# SenseBox-MCU-2-0.net
KiCad netlist of a schematic drawn in EAGLE
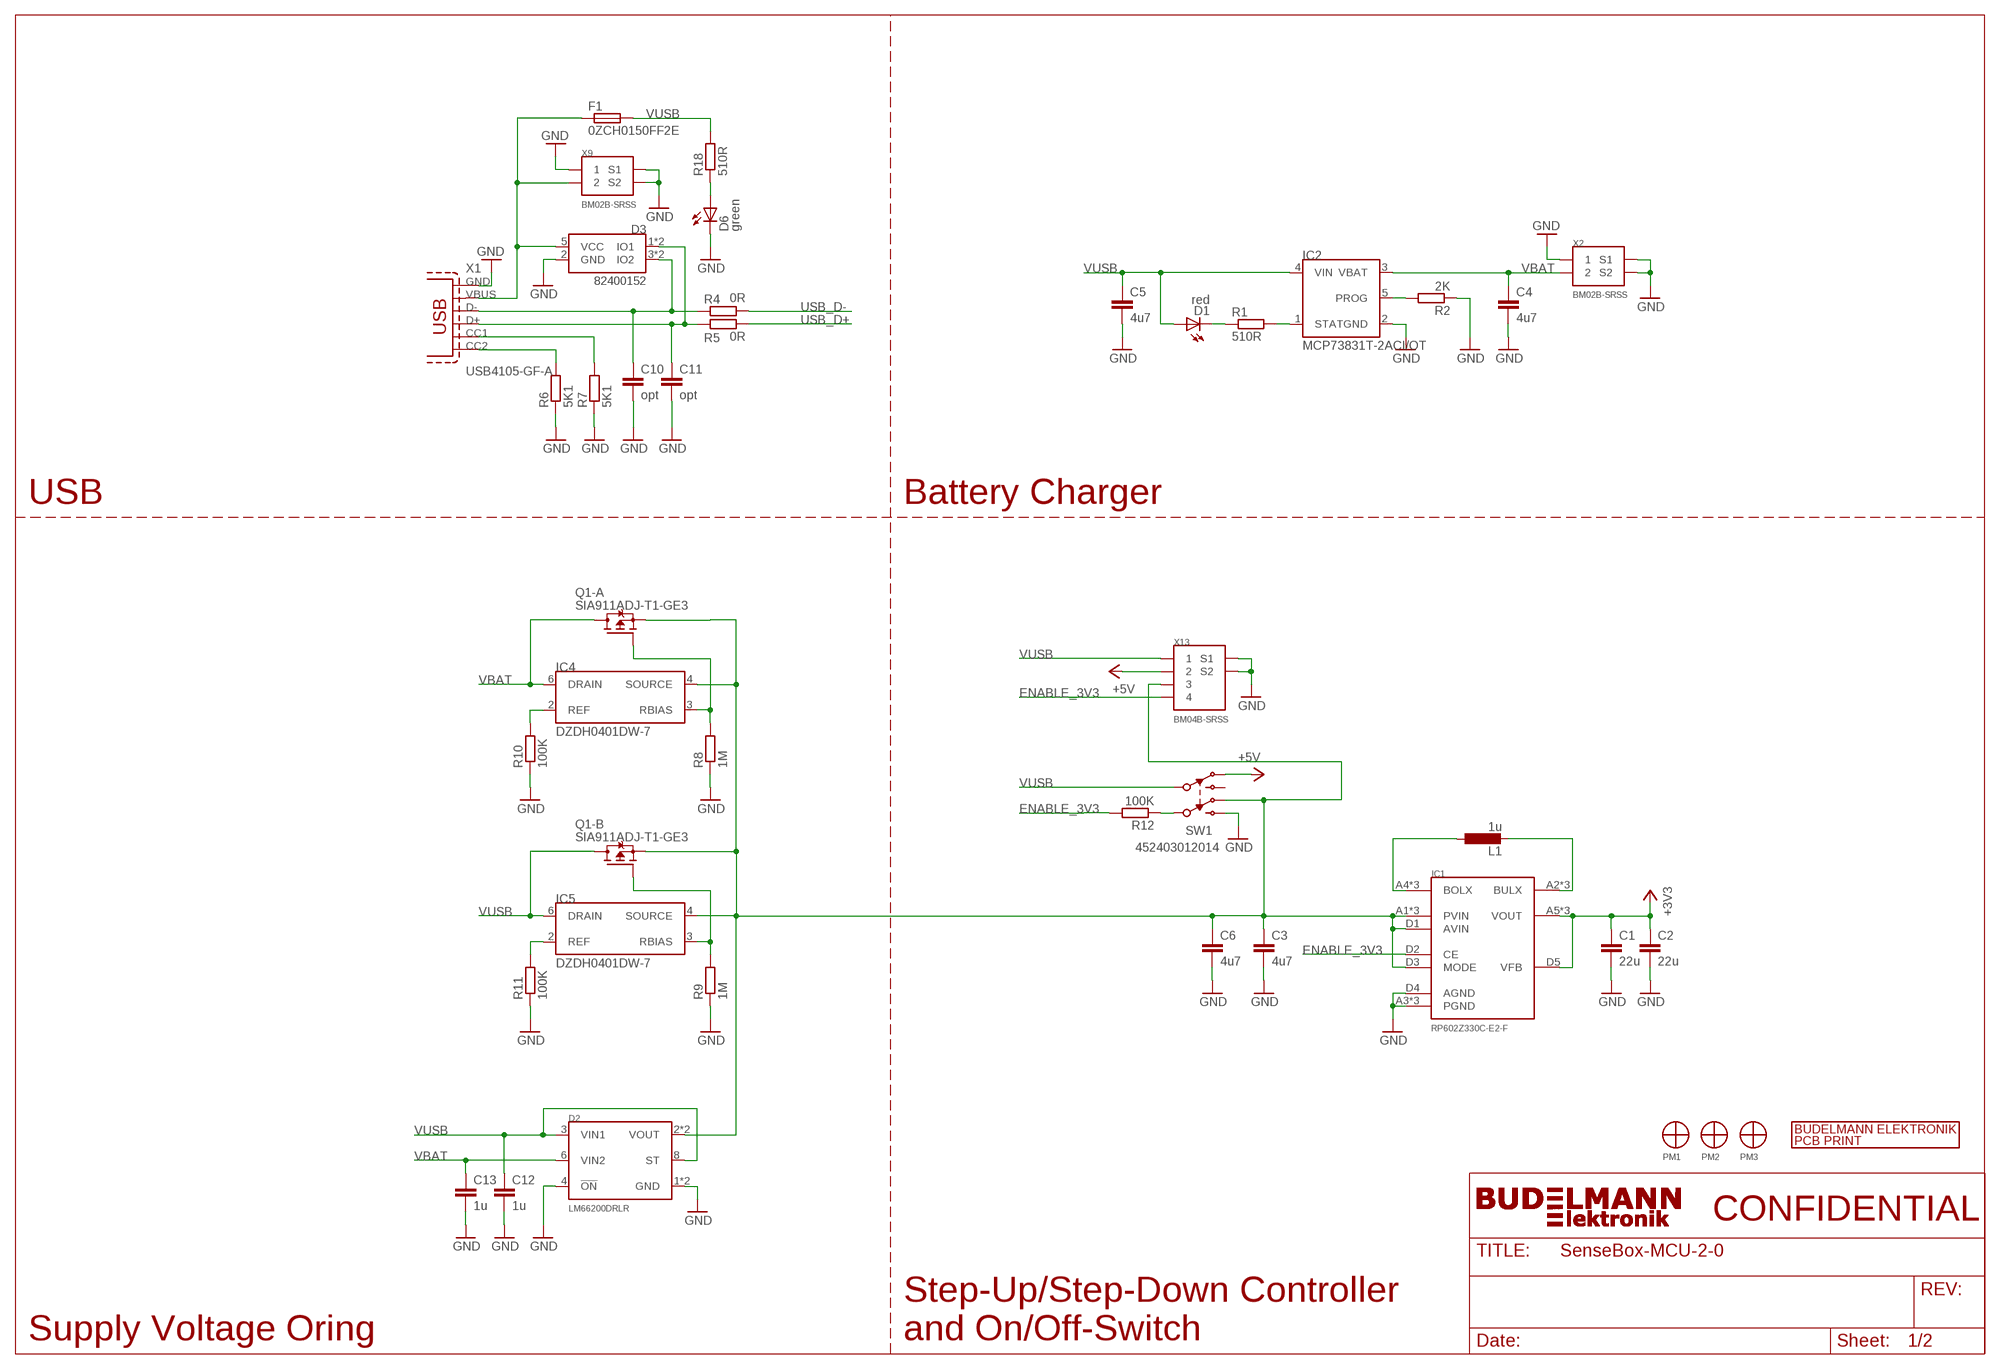
[diagram p0: schematic, sheet 1]
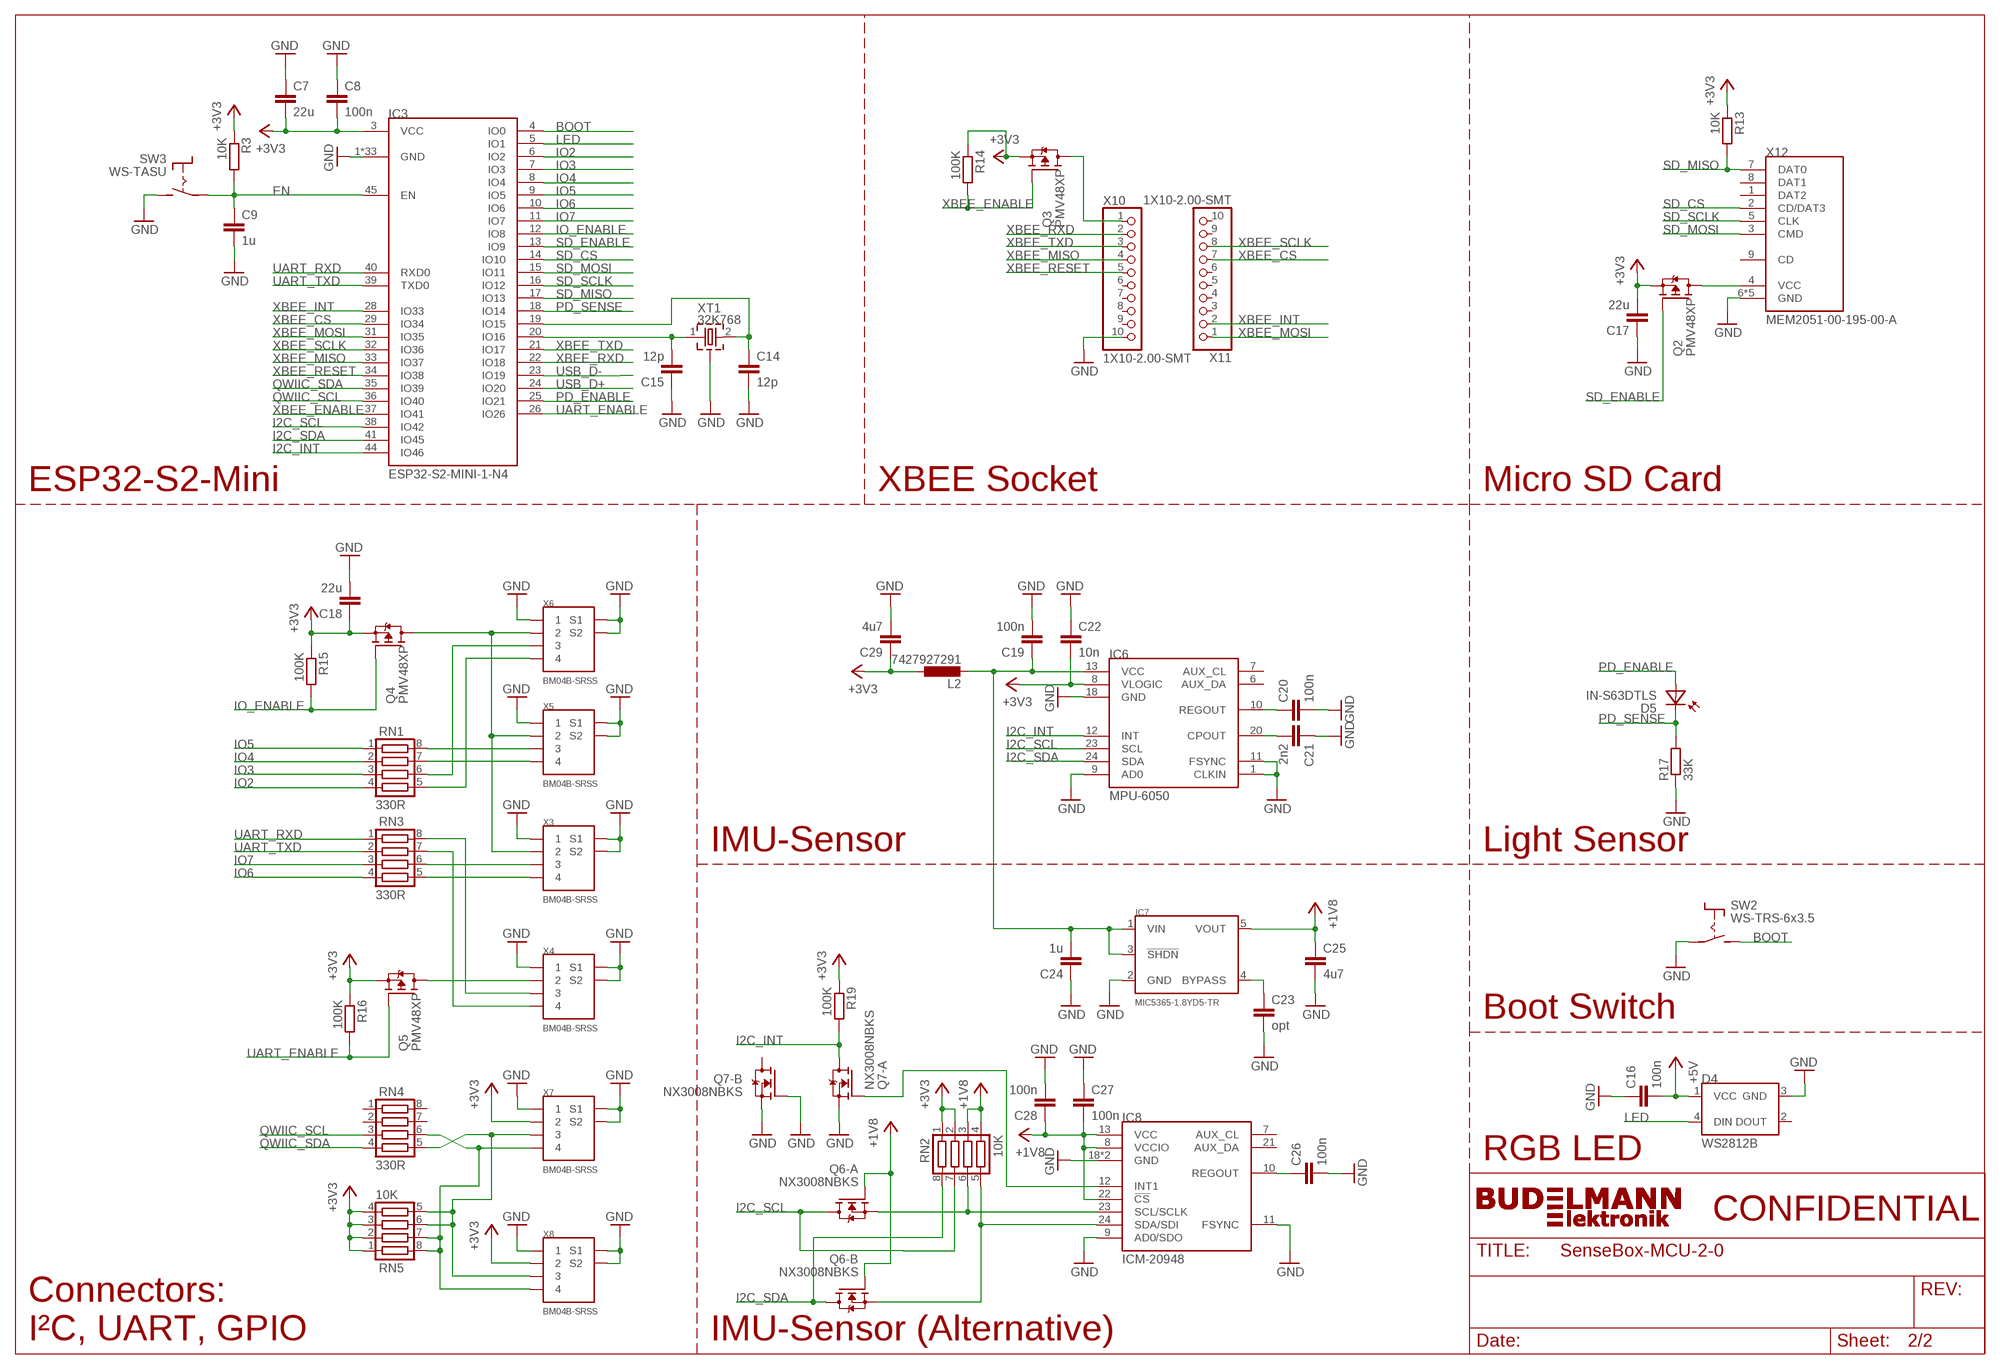
[diagram p1: schematic, sheet 2]

(export (version "E")
  (design (tool "Eeschema 10.0.6"))
  (components
    (comp (ref "C1")
      (value "22u")
      (footprint "eagle-import:0805N")
      (fields (field (name "VOLTAGE") "6V3"))
      (libsource (lib "eagle-import") (part "C_0805N_22U"))
    )
    (comp (ref "C2")
      (value "22u")
      (footprint "eagle-import:0805N")
      (fields (field (name "VOLTAGE") "6V3"))
      (libsource (lib "eagle-import") (part "C_0805N_22U"))
    )
    (comp (ref "C3")
      (value "4u7")
      (footprint "eagle-import:0603N")
      (fields (field (name "VOLTAGE") "6V3"))
      (libsource (lib "eagle-import") (part "C_0603N_4U7"))
    )
    (comp (ref "C4")
      (value "4u7")
      (footprint "eagle-import:0603N")
      (fields (field (name "VOLTAGE") "6V3"))
      (libsource (lib "eagle-import") (part "C_0603N_4U7"))
    )
    (comp (ref "C5")
      (value "4u7")
      (footprint "eagle-import:0603N")
      (fields (field (name "VOLTAGE") "6V3"))
      (libsource (lib "eagle-import") (part "C_0603N_4U7"))
    )
    (comp (ref "C6")
      (value "4u7")
      (footprint "eagle-import:0603N")
      (fields (field (name "VOLTAGE") "6V3"))
      (libsource (lib "eagle-import") (part "C_0603N_4U7"))
    )
    (comp (ref "C10")
      (value "opt")
      (footprint "eagle-import:0402N")
      (libsource (lib "eagle-import") (part "C_0402N"))
    )
    (comp (ref "C11")
      (value "opt")
      (footprint "eagle-import:0402N")
      (libsource (lib "eagle-import") (part "C_0402N"))
    )
    (comp (ref "C12")
      (value "1u")
      (footprint "eagle-import:0402N")
      (fields (field (name "VOLTAGE") "10"))
      (libsource (lib "eagle-import") (part "C_0402N_1U"))
    )
    (comp (ref "C13")
      (value "1u")
      (footprint "eagle-import:0402N")
      (fields (field (name "VOLTAGE") "10"))
      (libsource (lib "eagle-import") (part "C_0402N_1U"))
    )
    (comp (ref "D1")
      (value "red")
      (footprint "eagle-import:0603N")
      (libsource (lib "eagle-import") (part "LED_0603N_RED"))
    )
    (comp (ref "D2")
      (value "LM66200DRLR")
      (footprint "eagle-import:SOT-5X3")
      (libsource (lib "eagle-import") (part "LM66200"))
    )
    (comp (ref "D3")
      (value "82400152")
      (footprint "eagle-import:SOT563")
      (libsource (lib "eagle-import") (part "TVS-3-CHANNELS_SOT563_WE-TVS"))
    )
    (comp (ref "D6")
      (value "green")
      (footprint "eagle-import:0603N")
      (libsource (lib "eagle-import") (part "LED_0603N_GREEN"))
    )
    (comp (ref "F1")
      (value "0ZCH0150FF2E")
      (footprint "eagle-import:1210N")
      (libsource (lib "eagle-import") (part "FUSE-2PIN_1210N_1.5A"))
    )
    (comp (ref "IC1")
      (value "RP602Z330C-E2-F")
      (footprint "eagle-import:WLCSP-20-P1")
      (libsource (lib "eagle-import") (part "RP602_WLCSP-20-P1_RP602Z330C-E2-F"))
    )
    (comp (ref "IC2")
      (value "MCP73831T-2ACI/OT")
      (footprint "eagle-import:SOT23-5")
      (libsource (lib "eagle-import") (part "MCP73831_SOT23-5_MCP73831T-2ACI/OT"))
    )
    (comp (ref "IC4")
      (value "DZDH0401DW-7")
      (footprint "eagle-import:SOT363")
      (libsource (lib "eagle-import") (part "DZDH0401DW"))
    )
    (comp (ref "IC5")
      (value "DZDH0401DW-7")
      (footprint "eagle-import:SOT363")
      (libsource (lib "eagle-import") (part "DZDH0401DW"))
    )
    (comp (ref "L1")
      (value "1u")
      (footprint "eagle-import:5040")
      (libsource (lib "eagle-import") (part "L_5040_WE-LQS-1U"))
    )
    (comp (ref "PM1")
      (value "PM_ASSEMBLY")
      (footprint "eagle-import:PM1")
      (libsource (lib "eagle-import") (part "PM_ASSEMBLY"))
    )
    (comp (ref "PM2")
      (value "PM_ASSEMBLY")
      (footprint "eagle-import:PM1")
      (libsource (lib "eagle-import") (part "PM_ASSEMBLY"))
    )
    (comp (ref "PM3")
      (value "PM_ASSEMBLY")
      (footprint "eagle-import:PM1")
      (libsource (lib "eagle-import") (part "PM_ASSEMBLY"))
    )
    (comp (ref "Q1")
      (value "SIA911ADJ-T1-GE3")
      (footprint "eagle-import:POWERPAK-SC70-6")
      (fields (field (name "VOLTAGE") "20"))
      (libsource (lib "eagle-import") (part "MOSFET-P-DUAL_POWERPAK-SC70-6_SIA911ADJ-T1-GE3"))
    )
    (comp (ref "R1")
      (value "510R")
      (footprint "eagle-import:0402N")
      (fields (field (name "POWER") "0.063") (field (name "TOLERANCE") "1%") (field (name "VOLTAGE") "50"))
      (libsource (lib "eagle-import") (part "R_0402N_510R"))
    )
    (comp (ref "R2")
      (value "2K")
      (footprint "eagle-import:0402N")
      (fields (field (name "POWER") "0.063") (field (name "TOLERANCE") "1%") (field (name "VOLTAGE") "50"))
      (libsource (lib "eagle-import") (part "R_0402N_2K"))
    )
    (comp (ref "R4")
      (value "0R")
      (footprint "eagle-import:0402N")
      (libsource (lib "eagle-import") (part "R_0402N_0R"))
    )
    (comp (ref "R5")
      (value "0R")
      (footprint "eagle-import:0402N")
      (libsource (lib "eagle-import") (part "R_0402N_0R"))
    )
    (comp (ref "R6")
      (value "5K1")
      (footprint "eagle-import:0402N")
      (fields (field (name "POWER") "0.063") (field (name "TOLERANCE") "1%") (field (name "VOLTAGE") "50"))
      (libsource (lib "eagle-import") (part "R_0402N_5K1"))
    )
    (comp (ref "R7")
      (value "5K1")
      (footprint "eagle-import:0402N")
      (fields (field (name "POWER") "0.063") (field (name "TOLERANCE") "1%") (field (name "VOLTAGE") "50"))
      (libsource (lib "eagle-import") (part "R_0402N_5K1"))
    )
    (comp (ref "R8")
      (value "1M")
      (footprint "eagle-import:0402N")
      (fields (field (name "POWER") "0.063") (field (name "TOLERANCE") "1%") (field (name "VOLTAGE") "50"))
      (libsource (lib "eagle-import") (part "R_0402N_1M"))
    )
    (comp (ref "R9")
      (value "1M")
      (footprint "eagle-import:0402N")
      (fields (field (name "POWER") "0.063") (field (name "TOLERANCE") "1%") (field (name "VOLTAGE") "50"))
      (libsource (lib "eagle-import") (part "R_0402N_1M"))
    )
    (comp (ref "R10")
      (value "100K")
      (footprint "eagle-import:0402N")
      (fields (field (name "POWER") "0.063") (field (name "TOLERANCE") "1%") (field (name "VOLTAGE") "50"))
      (libsource (lib "eagle-import") (part "R_0402N_100K"))
    )
    (comp (ref "R11")
      (value "100K")
      (footprint "eagle-import:0402N")
      (fields (field (name "POWER") "0.063") (field (name "TOLERANCE") "1%") (field (name "VOLTAGE") "50"))
      (libsource (lib "eagle-import") (part "R_0402N_100K"))
    )
    (comp (ref "R12")
      (value "100K")
      (footprint "eagle-import:0402N")
      (fields (field (name "POWER") "0.063") (field (name "TOLERANCE") "1%") (field (name "VOLTAGE") "50"))
      (libsource (lib "eagle-import") (part "R_0402N_100K"))
    )
    (comp (ref "R18")
      (value "510R")
      (footprint "eagle-import:0402N")
      (fields (field (name "POWER") "0.063") (field (name "TOLERANCE") "1%") (field (name "VOLTAGE") "50"))
      (libsource (lib "eagle-import") (part "R_0402N_510R"))
    )
    (comp (ref "SW1")
      (value "452403012014")
      (footprint "eagle-import:WS-SLSV")
      (libsource (lib "eagle-import") (part "DPDT_WS-SLSV"))
    )
    (comp (ref "U$3")
      (value "BE_LOGO_10MM_T")
      (footprint "eagle-import:BE_TOP_10MM")
      (libsource (lib "eagle-import") (part "BE_LOGO_10MM_T"))
    )
    (comp (ref "X1")
      (value "USB4105-GF-A")
      (footprint "eagle-import:USB4105")
      (libsource (lib "eagle-import") (part "USB-C-2.0_USB4105_USB4105-GF-A"))
    )
    (comp (ref "X2")
      (value "BM02B-SRSS")
      (footprint "eagle-import:BM02B-SRSS")
      (libsource (lib "eagle-import") (part "SH-02_BM02B-SRSS_BM02B-SRSS"))
    )
    (comp (ref "X9")
      (value "BM02B-SRSS")
      (footprint "eagle-import:BM02B-SRSS")
      (libsource (lib "eagle-import") (part "SH-02_BM02B-SRSS_BM02B-SRSS"))
    )
    (comp (ref "X13")
      (value "BM04B-SRSS")
      (footprint "eagle-import:BM04B-SRSS")
      (libsource (lib "eagle-import") (part "SH-04_BM04B-SRSS_BM04B-SRSS"))
    )
    (comp (ref "C7")
      (value "22u")
      (footprint "eagle-import:0805N")
      (fields (field (name "VOLTAGE") "6V3"))
      (libsource (lib "eagle-import") (part "C_0805N_22U"))
    )
    (comp (ref "C8")
      (value "100n")
      (footprint "eagle-import:0402N")
      (fields (field (name "VOLTAGE") "16"))
      (libsource (lib "eagle-import") (part "C_0402N_100N"))
    )
    (comp (ref "C9")
      (value "1u")
      (footprint "eagle-import:0402N")
      (fields (field (name "VOLTAGE") "10"))
      (libsource (lib "eagle-import") (part "C_0402N_1U"))
    )
    (comp (ref "C14")
      (value "12p")
      (footprint "eagle-import:0402N")
      (fields (field (name "VOLTAGE") "50"))
      (libsource (lib "eagle-import") (part "C_0402N_12P"))
    )
    (comp (ref "C15")
      (value "12p")
      (footprint "eagle-import:0402N")
      (fields (field (name "VOLTAGE") "50"))
      (libsource (lib "eagle-import") (part "C_0402N_12P"))
    )
    (comp (ref "C16")
      (value "100n")
      (footprint "eagle-import:0402N")
      (fields (field (name "VOLTAGE") "16"))
      (libsource (lib "eagle-import") (part "C_0402N_100N"))
    )
    (comp (ref "C17")
      (value "22u")
      (footprint "eagle-import:0805N")
      (fields (field (name "VOLTAGE") "6V3"))
      (libsource (lib "eagle-import") (part "C_0805N_22U"))
    )
    (comp (ref "C18")
      (value "22u")
      (footprint "eagle-import:0805N")
      (fields (field (name "VOLTAGE") "6V3"))
      (libsource (lib "eagle-import") (part "C_0805N_22U"))
    )
    (comp (ref "C19")
      (value "100n")
      (footprint "eagle-import:0402N")
      (fields (field (name "VOLTAGE") "16"))
      (libsource (lib "eagle-import") (part "C_0402N_100N"))
    )
    (comp (ref "C20")
      (value "100n")
      (footprint "eagle-import:0402N")
      (fields (field (name "VOLTAGE") "16"))
      (libsource (lib "eagle-import") (part "C_0402N_100N"))
    )
    (comp (ref "C21")
      (value "2n2")
      (footprint "eagle-import:0402N")
      (fields (field (name "VOLTAGE") "50"))
      (libsource (lib "eagle-import") (part "C_0402N_2N2"))
    )
    (comp (ref "C22")
      (value "10n")
      (footprint "eagle-import:0402N")
      (fields (field (name "VOLTAGE") "25"))
      (libsource (lib "eagle-import") (part "C_0402N_10N"))
    )
    (comp (ref "C23")
      (value "opt")
      (footprint "eagle-import:0402N")
      (libsource (lib "eagle-import") (part "C_0402N"))
    )
    (comp (ref "C24")
      (value "1u")
      (footprint "eagle-import:0402N")
      (fields (field (name "VOLTAGE") "10"))
      (libsource (lib "eagle-import") (part "C_0402N_1U"))
    )
    (comp (ref "C25")
      (value "4u7")
      (footprint "eagle-import:0603N")
      (fields (field (name "VOLTAGE") "6V3"))
      (libsource (lib "eagle-import") (part "C_0603N_4U7"))
    )
    (comp (ref "C26")
      (value "100n")
      (footprint "eagle-import:0402N")
      (fields (field (name "VOLTAGE") "16"))
      (libsource (lib "eagle-import") (part "C_0402N_100N"))
    )
    (comp (ref "C27")
      (value "100n")
      (footprint "eagle-import:0402N")
      (fields (field (name "VOLTAGE") "16"))
      (libsource (lib "eagle-import") (part "C_0402N_100N"))
    )
    (comp (ref "C28")
      (value "100n")
      (footprint "eagle-import:0402N")
      (fields (field (name "VOLTAGE") "16"))
      (libsource (lib "eagle-import") (part "C_0402N_100N"))
    )
    (comp (ref "C29")
      (value "4u7")
      (footprint "eagle-import:0603N")
      (fields (field (name "VOLTAGE") "6V3"))
      (libsource (lib "eagle-import") (part "C_0603N_4U7"))
    )
    (comp (ref "D4")
      (value "WS2812B")
      (footprint "eagle-import:5050")
      (libsource (lib "eagle-import") (part "LED-ADRESSABLE_5050_WS2812B"))
    )
    (comp (ref "D5")
      (value "IN-S63DTLS")
      (footprint "eagle-import:0603N")
      (libsource (lib "eagle-import") (part "PHOTODIODE_0603N_IN-S63DTLS"))
    )
    (comp (ref "IC3")
      (value "ESP32-S2-MINI-1-N4")
      (footprint "eagle-import:ESP32-S2-MINI")
      (libsource (lib "eagle-import") (part "ESP32-S2-MINI_ESP32-S2-MINI_ESP32-S2-MINI-1-N4"))
    )
    (comp (ref "IC6")
      (value "MPU-6050")
      (footprint "eagle-import:QFN24_4X4")
      (libsource (lib "eagle-import") (part "MPU-6050"))
    )
    (comp (ref "IC7")
      (value "MIC5365-1.8YD5-TR")
      (footprint "eagle-import:SOT23-5")
      (fields (field (name "VOLTAGE") "1.8"))
      (libsource (lib "eagle-import") (part "FIX-5_SOT23-5_MIC5365-1.8YD5-TR"))
    )
    (comp (ref "IC8")
      (value "ICM-20948")
      (footprint "eagle-import:QFN24_3X3")
      (libsource (lib "eagle-import") (part "ICM-20948"))
    )
    (comp (ref "L2")
      (value "7427927291")
      (footprint "eagle-import:0402N")
      (libsource (lib "eagle-import") (part "L_0402N_WE-CBF-7427927291"))
    )
    (comp (ref "Q2")
      (value "PMV48XP")
      (footprint "eagle-import:SOT23")
      (fields (field (name "VOLTAGE") "20"))
      (libsource (lib "eagle-import") (part "MOSFET-P_SOT23'_PMV48XP"))
    )
    (comp (ref "Q3")
      (value "PMV48XP")
      (footprint "eagle-import:SOT23")
      (fields (field (name "VOLTAGE") "20"))
      (libsource (lib "eagle-import") (part "MOSFET-P_SOT23'_PMV48XP"))
    )
    (comp (ref "Q4")
      (value "PMV48XP")
      (footprint "eagle-import:SOT23")
      (fields (field (name "VOLTAGE") "20"))
      (libsource (lib "eagle-import") (part "MOSFET-P_SOT23'_PMV48XP"))
    )
    (comp (ref "Q5")
      (value "PMV48XP")
      (footprint "eagle-import:SOT23")
      (fields (field (name "VOLTAGE") "20"))
      (libsource (lib "eagle-import") (part "MOSFET-P_SOT23'_PMV48XP"))
    )
    (comp (ref "Q6")
      (value "NX3008NBKS")
      (footprint "eagle-import:SOT363")
      (fields (field (name "POWER") "0.3") (field (name "VOLTAGE") "30"))
      (libsource (lib "eagle-import") (part "MOSFET-N-DUAL_SOT363_NX3008NBKS"))
    )
    (comp (ref "Q7")
      (value "NX3008NBKS")
      (footprint "eagle-import:SOT363")
      (fields (field (name "POWER") "0.3") (field (name "VOLTAGE") "30"))
      (libsource (lib "eagle-import") (part "MOSFET-N-DUAL_SOT363_NX3008NBKS"))
    )
    (comp (ref "R3")
      (value "10K")
      (footprint "eagle-import:0402N")
      (fields (field (name "POWER") "0.063") (field (name "TOLERANCE") "1%") (field (name "VOLTAGE") "50"))
      (libsource (lib "eagle-import") (part "R_0402N_10K"))
    )
    (comp (ref "R13")
      (value "10K")
      (footprint "eagle-import:0402N")
      (fields (field (name "POWER") "0.063") (field (name "TOLERANCE") "1%") (field (name "VOLTAGE") "50"))
      (libsource (lib "eagle-import") (part "R_0402N_10K"))
    )
    (comp (ref "R14")
      (value "100K")
      (footprint "eagle-import:0402N")
      (fields (field (name "POWER") "0.063") (field (name "TOLERANCE") "1%") (field (name "VOLTAGE") "50"))
      (libsource (lib "eagle-import") (part "R_0402N_100K"))
    )
    (comp (ref "R15")
      (value "100K")
      (footprint "eagle-import:0402N")
      (fields (field (name "POWER") "0.063") (field (name "TOLERANCE") "1%") (field (name "VOLTAGE") "50"))
      (libsource (lib "eagle-import") (part "R_0402N_100K"))
    )
    (comp (ref "R16")
      (value "100K")
      (footprint "eagle-import:0402N")
      (fields (field (name "POWER") "0.063") (field (name "TOLERANCE") "1%") (field (name "VOLTAGE") "50"))
      (libsource (lib "eagle-import") (part "R_0402N_100K"))
    )
    (comp (ref "R17")
      (value "33K")
      (footprint "eagle-import:0402N")
      (fields (field (name "POWER") "0.063") (field (name "TOLERANCE") "1%") (field (name "VOLTAGE") "50"))
      (libsource (lib "eagle-import") (part "R_0402N_33K"))
    )
    (comp (ref "R19")
      (value "100K")
      (footprint "eagle-import:0402N")
      (fields (field (name "POWER") "0.063") (field (name "TOLERANCE") "1%") (field (name "VOLTAGE") "50"))
      (libsource (lib "eagle-import") (part "R_0402N_100K"))
    )
    (comp (ref "RN1")
      (value "330R")
      (footprint "eagle-import:CAY16")
      (fields (field (name "POWER") "0.062") (field (name "TOLERANCE") "5%") (field (name "VOLTAGE") "50"))
      (libsource (lib "eagle-import") (part "RN4_CAY16_330R"))
    )
    (comp (ref "RN2")
      (value "10K")
      (footprint "eagle-import:CAY16")
      (fields (field (name "POWER") "0.062") (field (name "TOLERANCE") "5%") (field (name "VOLTAGE") "50"))
      (libsource (lib "eagle-import") (part "RN4_CAY16_10K"))
    )
    (comp (ref "RN3")
      (value "330R")
      (footprint "eagle-import:CAY16")
      (fields (field (name "POWER") "0.062") (field (name "TOLERANCE") "5%") (field (name "VOLTAGE") "50"))
      (libsource (lib "eagle-import") (part "RN4_CAY16_330R"))
    )
    (comp (ref "RN4")
      (value "330R")
      (footprint "eagle-import:CAY16")
      (fields (field (name "POWER") "0.062") (field (name "TOLERANCE") "5%") (field (name "VOLTAGE") "50"))
      (libsource (lib "eagle-import") (part "RN4_CAY16_330R"))
    )
    (comp (ref "RN5")
      (value "10K")
      (footprint "eagle-import:CAY16")
      (fields (field (name "POWER") "0.062") (field (name "TOLERANCE") "5%") (field (name "VOLTAGE") "50"))
      (libsource (lib "eagle-import") (part "RN4_CAY16_10K"))
    )
    (comp (ref "SW2")
      (value "WS-TRS-6x3.5")
      (footprint "eagle-import:WS-TRS-6X3.5")
      (libsource (lib "eagle-import") (part "TACTILE_SWITCH_WS-TRS-6X3.5"))
    )
    (comp (ref "SW3")
      (value "WS-TASU")
      (footprint "eagle-import:WS-TASU")
      (libsource (lib "eagle-import") (part "TACTILE_SWITCH_WS-TASU"))
    )
    (comp (ref "X3")
      (value "BM04B-SRSS")
      (footprint "eagle-import:BM04B-SRSS")
      (libsource (lib "eagle-import") (part "SH-04_BM04B-SRSS_BM04B-SRSS"))
    )
    (comp (ref "X4")
      (value "BM04B-SRSS")
      (footprint "eagle-import:BM04B-SRSS")
      (libsource (lib "eagle-import") (part "SH-04_BM04B-SRSS_BM04B-SRSS"))
    )
    (comp (ref "X5")
      (value "BM04B-SRSS")
      (footprint "eagle-import:BM04B-SRSS")
      (libsource (lib "eagle-import") (part "SH-04_BM04B-SRSS_BM04B-SRSS"))
    )
    (comp (ref "X6")
      (value "BM04B-SRSS")
      (footprint "eagle-import:BM04B-SRSS")
      (libsource (lib "eagle-import") (part "SH-04_BM04B-SRSS_BM04B-SRSS"))
    )
    (comp (ref "X7")
      (value "BM04B-SRSS")
      (footprint "eagle-import:BM04B-SRSS")
      (libsource (lib "eagle-import") (part "SH-04_BM04B-SRSS_BM04B-SRSS"))
    )
    (comp (ref "X8")
      (value "BM04B-SRSS")
      (footprint "eagle-import:BM04B-SRSS")
      (libsource (lib "eagle-import") (part "SH-04_BM04B-SRSS_BM04B-SRSS"))
    )
    (comp (ref "X10")
      (value "1X10-2.00-SMT")
      (footprint "eagle-import:1X10-2.00-SMD")
      (libsource (lib "eagle-import") (part "1X10_2.00-SMT"))
    )
    (comp (ref "X11")
      (value "1X10-2.00-SMT")
      (footprint "eagle-import:1X10-2.00-SMD")
      (libsource (lib "eagle-import") (part "1X10_2.00-SMT"))
    )
    (comp (ref "X12")
      (value "MEM2051-00-195-00-A")
      (footprint "eagle-import:MEM2051")
      (libsource (lib "eagle-import") (part "SD-CARD2_MEM2051"))
    )
    (comp (ref "XT1")
      (value "32K768")
      (footprint "eagle-import:1.4X1.5X5.2")
      (libsource (lib "eagle-import") (part "CRYSTAL-1GND_1.4X1.5X5.2"))
    )
  )
  (nets
    (net (code "1") (name "+1V8") (class "Default")
      (node (ref "C25") (pin "1") (pinfunction "1_1") (pintype "passive"))
      (node (ref "C27") (pin "2") (pinfunction "2_2") (pintype "passive"))
      (node (ref "C28") (pin "1") (pinfunction "1_1") (pintype "passive"))
      (node (ref "IC7") (pin "5") (pinfunction "VOUT_5") (pintype "power_in"))
      (node (ref "IC8") (pin "13") (pinfunction "VCC_13") (pintype "power_in"))
      (node (ref "IC8") (pin "22") (pinfunction "~{CS}_22") (pintype "input"))
      (node (ref "IC8") (pin "8") (pinfunction "VCCIO_8") (pintype "power_in"))
      (node (ref "Q6") (pin "2") (pinfunction "G_2") (pintype "passive"))
      (node (ref "Q6") (pin "5") (pinfunction "G_5") (pintype "passive"))
      (node (ref "RN2") (pin "3") (pinfunction "3_3") (pintype "passive"))
      (node (ref "RN2") (pin "4") (pinfunction "4_4") (pintype "passive"))
    )
    (net (code "2") (name "+3V3") (class "Default")
      (node (ref "C1") (pin "1") (pinfunction "1_1") (pintype "passive"))
      (node (ref "C17") (pin "2") (pinfunction "2_2") (pintype "passive"))
      (node (ref "C18") (pin "1") (pinfunction "1_1") (pintype "passive"))
      (node (ref "C2") (pin "1") (pinfunction "1_1") (pintype "passive"))
      (node (ref "C22") (pin "2") (pinfunction "2_2") (pintype "passive"))
      (node (ref "C29") (pin "1") (pinfunction "1_1") (pintype "passive"))
      (node (ref "C7") (pin "2") (pinfunction "2_2") (pintype "passive"))
      (node (ref "C8") (pin "2") (pinfunction "2_2") (pintype "passive"))
      (node (ref "IC1") (pin "A5") (pinfunction "VOUT_A5") (pintype "power_in"))
      (node (ref "IC1") (pin "B5") (pinfunction "VOUT_B5") (pintype "power_in"))
      (node (ref "IC1") (pin "C5") (pinfunction "VOUT_C5") (pintype "power_in"))
      (node (ref "IC1") (pin "D5") (pinfunction "VFB_D5") (pintype "input"))
      (node (ref "IC3") (pin "3") (pinfunction "VCC_3") (pintype "power_in"))
      (node (ref "IC6") (pin "8") (pinfunction "VLOGIC_8") (pintype "power_in"))
      (node (ref "L2") (pin "1") (pinfunction "1_1") (pintype "passive"))
      (node (ref "Q2") (pin "2") (pinfunction "S_2") (pintype "passive"))
      (node (ref "Q3") (pin "2") (pinfunction "S_2") (pintype "passive"))
      (node (ref "Q4") (pin "2") (pinfunction "S_2") (pintype "passive"))
      (node (ref "Q5") (pin "2") (pinfunction "S_2") (pintype "passive"))
      (node (ref "R13") (pin "1") (pinfunction "1_1") (pintype "passive"))
      (node (ref "R14") (pin "1") (pinfunction "1_1") (pintype "passive"))
      (node (ref "R15") (pin "1") (pinfunction "1_1") (pintype "passive"))
      (node (ref "R16") (pin "1") (pinfunction "1_1") (pintype "passive"))
      (node (ref "R19") (pin "1") (pinfunction "1_1") (pintype "passive"))
      (node (ref "R3") (pin "1") (pinfunction "1_1") (pintype "passive"))
      (node (ref "RN2") (pin "1") (pinfunction "1_1") (pintype "passive"))
      (node (ref "RN2") (pin "2") (pinfunction "2_2") (pintype "passive"))
      (node (ref "RN5") (pin "1") (pinfunction "1_1") (pintype "passive"))
      (node (ref "RN5") (pin "2") (pinfunction "2_2") (pintype "passive"))
      (node (ref "RN5") (pin "3") (pinfunction "3_3") (pintype "passive"))
      (node (ref "RN5") (pin "4") (pinfunction "4_4") (pintype "passive"))
      (node (ref "X7") (pin "2") (pinfunction "2_2") (pintype "bidirectional"))
      (node (ref "X8") (pin "2") (pinfunction "2_2") (pintype "bidirectional"))
    )
    (net (code "3") (name "+5V") (class "Default")
      (node (ref "C16") (pin "2") (pinfunction "2_2") (pintype "passive"))
      (node (ref "D4") (pin "1") (pinfunction "VCC_1") (pintype "power_in"))
      (node (ref "SW1") (pin "3") (pinfunction "NC1_3") (pintype "bidirectional"))
      (node (ref "X13") (pin "2") (pinfunction "2_2") (pintype "bidirectional"))
    )
    (net (code "4") (name "BOOT") (class "Default")
      (node (ref "IC3") (pin "4") (pinfunction "IO0_4") (pintype "bidirectional"))
      (node (ref "SW2") (pin "2") (pinfunction "S_2") (pintype "passive"))
    )
    (net (code "5") (name "EN") (class "Default")
      (node (ref "C9") (pin "1") (pinfunction "1_1") (pintype "passive"))
      (node (ref "IC3") (pin "45") (pinfunction "EN_45") (pintype "input"))
      (node (ref "R3") (pin "2") (pinfunction "2_2") (pintype "passive"))
      (node (ref "SW3") (pin "1") (pinfunction "P_1") (pintype "passive"))
      (node (ref "SW3") (pin "3") (pinfunction "P_3") (pintype "passive"))
    )
    (net (code "6") (name "ENABLE_3V3") (class "Default")
      (node (ref "IC1") (pin "D2") (pinfunction "CE_D2") (pintype "input"))
      (node (ref "R12") (pin "2") (pinfunction "2_2") (pintype "passive"))
      (node (ref "X13") (pin "4") (pinfunction "4_4") (pintype "bidirectional"))
    )
    (net (code "7") (name "GND") (class "Default")
      (node (ref "C1") (pin "2") (pinfunction "2_2") (pintype "passive"))
      (node (ref "C10") (pin "2") (pinfunction "2_2") (pintype "passive"))
      (node (ref "C11") (pin "2") (pinfunction "2_2") (pintype "passive"))
      (node (ref "C12") (pin "2") (pinfunction "2_2") (pintype "passive"))
      (node (ref "C13") (pin "2") (pinfunction "2_2") (pintype "passive"))
      (node (ref "C14") (pin "2") (pinfunction "2_2") (pintype "passive"))
      (node (ref "C15") (pin "1") (pinfunction "1_1") (pintype "passive"))
      (node (ref "C16") (pin "1") (pinfunction "1_1") (pintype "passive"))
      (node (ref "C17") (pin "1") (pinfunction "1_1") (pintype "passive"))
      (node (ref "C18") (pin "2") (pinfunction "2_2") (pintype "passive"))
      (node (ref "C19") (pin "2") (pinfunction "2_2") (pintype "passive"))
      (node (ref "C2") (pin "2") (pinfunction "2_2") (pintype "passive"))
      (node (ref "C20") (pin "2") (pinfunction "2_2") (pintype "passive"))
      (node (ref "C21") (pin "1") (pinfunction "1_1") (pintype "passive"))
      (node (ref "C22") (pin "1") (pinfunction "1_1") (pintype "passive"))
      (node (ref "C23") (pin "2") (pinfunction "2_2") (pintype "passive"))
      (node (ref "C24") (pin "1") (pinfunction "1_1") (pintype "passive"))
      (node (ref "C25") (pin "2") (pinfunction "2_2") (pintype "passive"))
      (node (ref "C26") (pin "2") (pinfunction "2_2") (pintype "passive"))
      (node (ref "C27") (pin "1") (pinfunction "1_1") (pintype "passive"))
      (node (ref "C28") (pin "2") (pinfunction "2_2") (pintype "passive"))
      (node (ref "C29") (pin "2") (pinfunction "2_2") (pintype "passive"))
      (node (ref "C3") (pin "2") (pinfunction "2_2") (pintype "passive"))
      (node (ref "C4") (pin "2") (pinfunction "2_2") (pintype "passive"))
      (node (ref "C5") (pin "2") (pinfunction "2_2") (pintype "passive"))
      (node (ref "C6") (pin "2") (pinfunction "2_2") (pintype "passive"))
      (node (ref "C7") (pin "1") (pinfunction "1_1") (pintype "passive"))
      (node (ref "C8") (pin "1") (pinfunction "1_1") (pintype "passive"))
      (node (ref "C9") (pin "2") (pinfunction "2_2") (pintype "passive"))
      (node (ref "D2") (pin "1") (pinfunction "GND_1") (pintype "power_in"))
      (node (ref "D2") (pin "4") (pinfunction "~{ON}_4") (pintype "input"))
      (node (ref "D2") (pin "5") (pinfunction "GND_5") (pintype "power_in"))
      (node (ref "D3") (pin "2") (pinfunction "GND_2") (pintype "power_in"))
      (node (ref "D4") (pin "3") (pinfunction "GND_3") (pintype "power_in"))
      (node (ref "D6") (pin "C") (pinfunction "C_C") (pintype "passive"))
      (node (ref "IC1") (pin "A3") (pinfunction "PGND_A3") (pintype "power_in"))
      (node (ref "IC1") (pin "B3") (pinfunction "PGND_B3") (pintype "power_in"))
      (node (ref "IC1") (pin "C3") (pinfunction "PGND_C3") (pintype "power_in"))
      (node (ref "IC1") (pin "D4") (pinfunction "AGND_D4") (pintype "power_in"))
      (node (ref "IC2") (pin "2") (pinfunction "GND_2") (pintype "power_in"))
      (node (ref "IC3") (pin "1") (pinfunction "GND_1") (pintype "power_in"))
      (node (ref "IC3") (pin "2") (pinfunction "GND_2") (pintype "power_in"))
      (node (ref "IC3") (pin "30") (pinfunction "GND_30") (pintype "power_in"))
      (node (ref "IC3") (pin "42") (pinfunction "GND_42") (pintype "power_in"))
      (node (ref "IC3") (pin "43") (pinfunction "GND_43") (pintype "power_in"))
      (node (ref "IC3") (pin "46") (pinfunction "GND_46") (pintype "power_in"))
      (node (ref "IC3") (pin "47") (pinfunction "GND_47") (pintype "power_in"))
      (node (ref "IC3") (pin "48") (pinfunction "GND_48") (pintype "power_in"))
      (node (ref "IC3") (pin "49") (pinfunction "GND_49") (pintype "power_in"))
      (node (ref "IC3") (pin "50") (pinfunction "GND_50") (pintype "power_in"))
      (node (ref "IC3") (pin "51") (pinfunction "GND_51") (pintype "power_in"))
      (node (ref "IC3") (pin "52") (pinfunction "GND_52") (pintype "power_in"))
      (node (ref "IC3") (pin "53") (pinfunction "GND_53") (pintype "power_in"))
      (node (ref "IC3") (pin "54") (pinfunction "GND_54") (pintype "power_in"))
      (node (ref "IC3") (pin "55") (pinfunction "GND_55") (pintype "power_in"))
      (node (ref "IC3") (pin "56") (pinfunction "GND_56") (pintype "power_in"))
      (node (ref "IC3") (pin "57") (pinfunction "GND_57") (pintype "power_in"))
      (node (ref "IC3") (pin "58") (pinfunction "GND_58") (pintype "power_in"))
      (node (ref "IC3") (pin "59") (pinfunction "GND_59") (pintype "power_in"))
      (node (ref "IC3") (pin "60") (pinfunction "GND_60") (pintype "power_in"))
      (node (ref "IC3") (pin "61") (pinfunction "GND_61") (pintype "power_in"))
      (node (ref "IC3") (pin "62") (pinfunction "GND_62") (pintype "power_in"))
      (node (ref "IC3") (pin "63") (pinfunction "GND_63") (pintype "power_in"))
      (node (ref "IC3") (pin "64") (pinfunction "GND_64") (pintype "power_in"))
      (node (ref "IC3") (pin "65") (pinfunction "GND_65") (pintype "power_in"))
      (node (ref "IC3") (pin "66") (pinfunction "GND_66") (pintype "power_in"))
      (node (ref "IC3") (pin "67") (pinfunction "GND_67") (pintype "power_in"))
      (node (ref "IC3") (pin "68") (pinfunction "GND_68") (pintype "power_in"))
      (node (ref "IC3") (pin "69") (pinfunction "GND_69") (pintype "power_in"))
      (node (ref "IC3") (pin "70") (pinfunction "GND_70") (pintype "power_in"))
      (node (ref "IC3") (pin "71") (pinfunction "GND_71") (pintype "power_in"))
      (node (ref "IC3") (pin "72") (pinfunction "GND_72") (pintype "power_in"))
      (node (ref "IC3") (pin "73") (pinfunction "GND_73") (pintype "power_in"))
      (node (ref "IC6") (pin "1") (pinfunction "CLKIN_1") (pintype "input"))
      (node (ref "IC6") (pin "11") (pinfunction "FSYNC_11") (pintype "input"))
      (node (ref "IC6") (pin "18") (pinfunction "GND_18") (pintype "power_in"))
      (node (ref "IC6") (pin "9") (pinfunction "AD0_9") (pintype "input"))
      (node (ref "IC7") (pin "2") (pinfunction "GND_2") (pintype "power_in"))
      (node (ref "IC8") (pin "11") (pinfunction "FSYNC_11") (pintype "input"))
      (node (ref "IC8") (pin "18") (pinfunction "GND_18") (pintype "power_in"))
      (node (ref "IC8") (pin "20") (pinfunction "GND_20") (pintype "power_in"))
      (node (ref "IC8") (pin "9") (pinfunction "AD0/SDO_9") (pintype "input"))
      (node (ref "Q7") (pin "1") (pinfunction "S_1") (pintype "passive"))
      (node (ref "Q7") (pin "4") (pinfunction "S_4") (pintype "passive"))
      (node (ref "Q7") (pin "5") (pinfunction "G_5") (pintype "passive"))
      (node (ref "R10") (pin "1") (pinfunction "1_1") (pintype "passive"))
      (node (ref "R11") (pin "1") (pinfunction "1_1") (pintype "passive"))
      (node (ref "R17") (pin "1") (pinfunction "1_1") (pintype "passive"))
      (node (ref "R2") (pin "1") (pinfunction "1_1") (pintype "passive"))
      (node (ref "R6") (pin "1") (pinfunction "1_1") (pintype "passive"))
      (node (ref "R7") (pin "1") (pinfunction "1_1") (pintype "passive"))
      (node (ref "R8") (pin "1") (pinfunction "1_1") (pintype "passive"))
      (node (ref "R9") (pin "1") (pinfunction "1_1") (pintype "passive"))
      (node (ref "SW1") (pin "4") (pinfunction "NO2_4") (pintype "bidirectional"))
      (node (ref "SW2") (pin "1") (pinfunction "P_1") (pintype "passive"))
      (node (ref "SW3") (pin "2") (pinfunction "S_2") (pintype "passive"))
      (node (ref "SW3") (pin "4") (pinfunction "S_4") (pintype "passive"))
      (node (ref "X1") (pin "A1_B12") (pinfunction "GND_A1_B12") (pintype "power_in"))
      (node (ref "X1") (pin "B1_A12") (pinfunction "GND_B1_A12") (pintype "power_in"))
      (node (ref "X1") (pin "S1") (pinfunction "GND_S1") (pintype "power_in"))
      (node (ref "X1") (pin "S2") (pinfunction "GND_S2") (pintype "power_in"))
      (node (ref "X1") (pin "S3") (pinfunction "GND_S3") (pintype "power_in"))
      (node (ref "X1") (pin "S4") (pinfunction "GND_S4") (pintype "power_in"))
      (node (ref "X10") (pin "10") (pinfunction "10_10") (pintype "passive"))
      (node (ref "X12") (pin "6") (pinfunction "GND_6") (pintype "power_in"))
      (node (ref "X12") (pin "S1") (pinfunction "GND_S1") (pintype "power_in"))
      (node (ref "X12") (pin "S2") (pinfunction "GND_S2") (pintype "power_in"))
      (node (ref "X12") (pin "S3") (pinfunction "GND_S3") (pintype "power_in"))
      (node (ref "X12") (pin "S4") (pinfunction "GND_S4") (pintype "power_in"))
      (node (ref "X13") (pin "S1") (pinfunction "S1_S1") (pintype "bidirectional"))
      (node (ref "X13") (pin "S2") (pinfunction "S2_S2") (pintype "bidirectional"))
      (node (ref "X2") (pin "1") (pinfunction "1_1") (pintype "bidirectional"))
      (node (ref "X2") (pin "S1") (pinfunction "S1_S1") (pintype "bidirectional"))
      (node (ref "X2") (pin "S2") (pinfunction "S2_S2") (pintype "bidirectional"))
      (node (ref "X3") (pin "1") (pinfunction "1_1") (pintype "bidirectional"))
      (node (ref "X3") (pin "S1") (pinfunction "S1_S1") (pintype "bidirectional"))
      (node (ref "X3") (pin "S2") (pinfunction "S2_S2") (pintype "bidirectional"))
      (node (ref "X4") (pin "1") (pinfunction "1_1") (pintype "bidirectional"))
      (node (ref "X4") (pin "S1") (pinfunction "S1_S1") (pintype "bidirectional"))
      (node (ref "X4") (pin "S2") (pinfunction "S2_S2") (pintype "bidirectional"))
      (node (ref "X5") (pin "1") (pinfunction "1_1") (pintype "bidirectional"))
      (node (ref "X5") (pin "S1") (pinfunction "S1_S1") (pintype "bidirectional"))
      (node (ref "X5") (pin "S2") (pinfunction "S2_S2") (pintype "bidirectional"))
      (node (ref "X6") (pin "1") (pinfunction "1_1") (pintype "bidirectional"))
      (node (ref "X6") (pin "S1") (pinfunction "S1_S1") (pintype "bidirectional"))
      (node (ref "X6") (pin "S2") (pinfunction "S2_S2") (pintype "bidirectional"))
      (node (ref "X7") (pin "1") (pinfunction "1_1") (pintype "bidirectional"))
      (node (ref "X7") (pin "S1") (pinfunction "S1_S1") (pintype "bidirectional"))
      (node (ref "X7") (pin "S2") (pinfunction "S2_S2") (pintype "bidirectional"))
      (node (ref "X8") (pin "1") (pinfunction "1_1") (pintype "bidirectional"))
      (node (ref "X8") (pin "S1") (pinfunction "S1_S1") (pintype "bidirectional"))
      (node (ref "X8") (pin "S2") (pinfunction "S2_S2") (pintype "bidirectional"))
      (node (ref "X9") (pin "1") (pinfunction "1_1") (pintype "bidirectional"))
      (node (ref "X9") (pin "S1") (pinfunction "S1_S1") (pintype "bidirectional"))
      (node (ref "X9") (pin "S2") (pinfunction "S2_S2") (pintype "bidirectional"))
      (node (ref "XT1") (pin "3") (pinfunction "GND_3") (pintype "power_in"))
    )
    (net (code "8") (name "I2C_INT") (class "Default")
      (node (ref "IC3") (pin "44") (pinfunction "IO46_44") (pintype "input"))
      (node (ref "IC6") (pin "12") (pinfunction "INT_12") (pintype "open_collector"))
      (node (ref "Q7") (pin "6") (pinfunction "D_6") (pintype "passive"))
      (node (ref "R19") (pin "2") (pinfunction "2_2") (pintype "passive"))
    )
    (net (code "9") (name "I2C_SCL") (class "Default")
      (node (ref "IC3") (pin "38") (pinfunction "IO42_38") (pintype "bidirectional"))
      (node (ref "IC6") (pin "23") (pinfunction "SCL_23") (pintype "bidirectional"))
      (node (ref "Q6") (pin "6") (pinfunction "D_6") (pintype "passive"))
      (node (ref "RN2") (pin "7") (pinfunction "7_7") (pintype "passive"))
    )
    (net (code "10") (name "I2C_SDA") (class "Default")
      (node (ref "IC3") (pin "41") (pinfunction "IO45_41") (pintype "bidirectional"))
      (node (ref "IC6") (pin "24") (pinfunction "SDA_24") (pintype "bidirectional"))
      (node (ref "Q6") (pin "3") (pinfunction "D_3") (pintype "passive"))
      (node (ref "RN2") (pin "8") (pinfunction "8_8") (pintype "passive"))
    )
    (net (code "11") (name "IO2") (class "Default")
      (node (ref "IC3") (pin "6") (pinfunction "IO2_6") (pintype "bidirectional"))
      (node (ref "RN1") (pin "4") (pinfunction "4_4") (pintype "passive"))
    )
    (net (code "12") (name "IO3") (class "Default")
      (node (ref "IC3") (pin "7") (pinfunction "IO3_7") (pintype "bidirectional"))
      (node (ref "RN1") (pin "3") (pinfunction "3_3") (pintype "passive"))
    )
    (net (code "13") (name "IO4") (class "Default")
      (node (ref "IC3") (pin "8") (pinfunction "IO4_8") (pintype "bidirectional"))
      (node (ref "RN1") (pin "2") (pinfunction "2_2") (pintype "passive"))
    )
    (net (code "14") (name "IO5") (class "Default")
      (node (ref "IC3") (pin "9") (pinfunction "IO5_9") (pintype "bidirectional"))
      (node (ref "RN1") (pin "1") (pinfunction "1_1") (pintype "passive"))
    )
    (net (code "15") (name "IO6") (class "Default")
      (node (ref "IC3") (pin "10") (pinfunction "IO6_10") (pintype "bidirectional"))
      (node (ref "RN3") (pin "4") (pinfunction "4_4") (pintype "passive"))
    )
    (net (code "16") (name "IO7") (class "Default")
      (node (ref "IC3") (pin "11") (pinfunction "IO7_11") (pintype "bidirectional"))
      (node (ref "RN3") (pin "3") (pinfunction "3_3") (pintype "passive"))
    )
    (net (code "17") (name "IO_ENABLE") (class "Default")
      (node (ref "IC3") (pin "12") (pinfunction "IO8_12") (pintype "bidirectional"))
      (node (ref "Q4") (pin "1") (pinfunction "G_1") (pintype "passive"))
      (node (ref "R15") (pin "2") (pinfunction "2_2") (pintype "passive"))
    )
    (net (code "18") (name "LED") (class "Default")
      (node (ref "D4") (pin "4") (pinfunction "DIN_4") (pintype "input"))
      (node (ref "IC3") (pin "5") (pinfunction "IO1_5") (pintype "bidirectional"))
    )
    (net (code "19") (name "Net-(C10-Pad1)") (class "Default")
      (node (ref "C10") (pin "1") (pinfunction "1_1") (pintype "passive"))
      (node (ref "D3") (pin "3") (pinfunction "IO2_3") (pintype "passive"))
      (node (ref "D3") (pin "4") (pinfunction "IO2_4") (pintype "passive"))
      (node (ref "R4") (pin "1") (pinfunction "1_1") (pintype "passive"))
      (node (ref "X1") (pin "A7") (pinfunction "D-_A7") (pintype "bidirectional"))
      (node (ref "X1") (pin "B7") (pinfunction "D-_B7") (pintype "bidirectional"))
    )
    (net (code "20") (name "Net-(C11-Pad1)") (class "Default")
      (node (ref "C11") (pin "1") (pinfunction "1_1") (pintype "passive"))
      (node (ref "D3") (pin "1") (pinfunction "IO1_1") (pintype "passive"))
      (node (ref "D3") (pin "6") (pinfunction "IO1_6") (pintype "passive"))
      (node (ref "R5") (pin "1") (pinfunction "1_1") (pintype "passive"))
      (node (ref "X1") (pin "A6") (pinfunction "D+_A6") (pintype "bidirectional"))
      (node (ref "X1") (pin "B6") (pinfunction "D+_B6") (pintype "bidirectional"))
    )
    (net (code "21") (name "Net-(D1-PadC)") (class "Default")
      (node (ref "D1") (pin "C") (pinfunction "C_C") (pintype "passive"))
      (node (ref "R1") (pin "1") (pinfunction "1_1") (pintype "passive"))
    )
    (net (code "22") (name "Net-(D3-VCC)") (class "Default")
      (node (ref "D3") (pin "5") (pinfunction "VCC_5") (pintype "power_in"))
      (node (ref "F1") (pin "1") (pinfunction "2_1") (pintype "passive"))
      (node (ref "X1") (pin "A4_B9") (pinfunction "VBUS_A4_B9") (pintype "power_in"))
      (node (ref "X1") (pin "B4_A9") (pinfunction "VBUS_B4_A9") (pintype "power_in"))
      (node (ref "X9") (pin "2") (pinfunction "2_2") (pintype "bidirectional"))
    )
    (net (code "23") (name "Net-(D6-PadA)") (class "Default")
      (node (ref "D6") (pin "A") (pinfunction "A_A") (pintype "passive"))
      (node (ref "R18") (pin "1") (pinfunction "1_1") (pintype "passive"))
    )
    (net (code "24") (name "Net-(IC1-AVIN)") (class "Default")
      (node (ref "C3") (pin "1") (pinfunction "1_1") (pintype "passive"))
      (node (ref "C6") (pin "1") (pinfunction "1_1") (pintype "passive"))
      (node (ref "D2") (pin "2") (pinfunction "VOUT_2") (pintype "power_in"))
      (node (ref "D2") (pin "7") (pinfunction "VOUT_7") (pintype "power_in"))
      (node (ref "IC1") (pin "A1") (pinfunction "PVIN_A1") (pintype "power_in"))
      (node (ref "IC1") (pin "B1") (pinfunction "PVIN_B1") (pintype "power_in"))
      (node (ref "IC1") (pin "C1") (pinfunction "PVIN_C1") (pintype "power_in"))
      (node (ref "IC1") (pin "D1") (pinfunction "AVIN_D1") (pintype "power_in"))
      (node (ref "IC1") (pin "D3") (pinfunction "MODE_D3") (pintype "input"))
      (node (ref "IC4") (pin "4") (pinfunction "SOURCE_4") (pintype "passive"))
      (node (ref "IC5") (pin "4") (pinfunction "SOURCE_4") (pintype "passive"))
      (node (ref "Q1") (pin "1") (pinfunction "S_1") (pintype "passive"))
      (node (ref "Q1") (pin "4") (pinfunction "S_4") (pintype "passive"))
      (node (ref "SW1") (pin "6") (pinfunction "NC2_6") (pintype "bidirectional"))
      (node (ref "X13") (pin "3") (pinfunction "3_3") (pintype "bidirectional"))
    )
    (net (code "25") (name "Net-(IC1-BOLX-PadA4)") (class "Default")
      (node (ref "IC1") (pin "A4") (pinfunction "BOLX_A4") (pintype "output"))
      (node (ref "IC1") (pin "B4") (pinfunction "BOLX_B4") (pintype "output"))
      (node (ref "IC1") (pin "C4") (pinfunction "BOLX_C4") (pintype "output"))
      (node (ref "L1") (pin "1") (pinfunction "1_1") (pintype "passive"))
    )
    (net (code "26") (name "Net-(IC1-BULX-PadA2)") (class "Default")
      (node (ref "IC1") (pin "A2") (pinfunction "BULX_A2") (pintype "output"))
      (node (ref "IC1") (pin "B2") (pinfunction "BULX_B2") (pintype "output"))
      (node (ref "IC1") (pin "C2") (pinfunction "BULX_C2") (pintype "output"))
      (node (ref "L1") (pin "2") (pinfunction "2_2") (pintype "passive"))
    )
    (net (code "27") (name "Net-(IC2-PROG)") (class "Default")
      (node (ref "IC2") (pin "5") (pinfunction "PROG_5") (pintype "input"))
      (node (ref "R2") (pin "2") (pinfunction "2_2") (pintype "passive"))
    )
    (net (code "28") (name "Net-(IC2-STAT)") (class "Default")
      (node (ref "IC2") (pin "1") (pinfunction "STAT_1") (pintype "open_collector"))
      (node (ref "R1") (pin "2") (pinfunction "2_2") (pintype "passive"))
    )
    (net (code "29") (name "Net-(IC3-IO15)") (class "Default")
      (node (ref "C14") (pin "1") (pinfunction "1_1") (pintype "passive"))
      (node (ref "IC3") (pin "19") (pinfunction "IO15_19") (pintype "bidirectional"))
      (node (ref "XT1") (pin "2") (pinfunction "2_2") (pintype "passive"))
    )
    (net (code "30") (name "Net-(IC3-IO16)") (class "Default")
      (node (ref "C15") (pin "2") (pinfunction "2_2") (pintype "passive"))
      (node (ref "IC3") (pin "20") (pinfunction "IO16_20") (pintype "bidirectional"))
      (node (ref "XT1") (pin "1") (pinfunction "1_1") (pintype "passive"))
    )
    (net (code "31") (name "Net-(IC4-RBIAS)") (class "Default")
      (node (ref "IC4") (pin "3") (pinfunction "RBIAS_3") (pintype "passive"))
      (node (ref "Q1") (pin "2") (pinfunction "G_2") (pintype "passive"))
      (node (ref "R8") (pin "2") (pinfunction "2_2") (pintype "passive"))
    )
    (net (code "32") (name "Net-(IC4-REF)") (class "Default")
      (node (ref "IC4") (pin "2") (pinfunction "REF_2") (pintype "input"))
      (node (ref "R10") (pin "2") (pinfunction "2_2") (pintype "passive"))
    )
    (net (code "33") (name "Net-(IC5-RBIAS)") (class "Default")
      (node (ref "IC5") (pin "3") (pinfunction "RBIAS_3") (pintype "passive"))
      (node (ref "Q1") (pin "5") (pinfunction "G_5") (pintype "passive"))
      (node (ref "R9") (pin "2") (pinfunction "2_2") (pintype "passive"))
    )
    (net (code "34") (name "Net-(IC5-REF)") (class "Default")
      (node (ref "IC5") (pin "2") (pinfunction "REF_2") (pintype "input"))
      (node (ref "R11") (pin "2") (pinfunction "2_2") (pintype "passive"))
    )
    (net (code "35") (name "Net-(IC6-CPOUT)") (class "Default")
      (node (ref "C21") (pin "2") (pinfunction "2_2") (pintype "passive"))
      (node (ref "IC6") (pin "20") (pinfunction "CPOUT_20") (pintype "output"))
    )
    (net (code "36") (name "Net-(IC6-REGOUT)") (class "Default")
      (node (ref "C20") (pin "1") (pinfunction "1_1") (pintype "passive"))
      (node (ref "IC6") (pin "10") (pinfunction "REGOUT_10") (pintype "output"))
    )
    (net (code "37") (name "Net-(IC6-VCC)") (class "Default")
      (node (ref "C19") (pin "1") (pinfunction "1_1") (pintype "passive"))
      (node (ref "C24") (pin "2") (pinfunction "2_2") (pintype "passive"))
      (node (ref "IC6") (pin "13") (pinfunction "VCC_13") (pintype "power_in"))
      (node (ref "IC7") (pin "1") (pinfunction "VIN_1") (pintype "power_in"))
      (node (ref "IC7") (pin "3") (pinfunction "~{SHDN}_3") (pintype "input"))
      (node (ref "L2") (pin "2") (pinfunction "2_2") (pintype "passive"))
    )
    (net (code "38") (name "Net-(IC7-BYPASS)") (class "Default")
      (node (ref "C23") (pin "1") (pinfunction "1_1") (pintype "passive"))
      (node (ref "IC7") (pin "4") (pinfunction "BYPASS_4") (pintype "passive"))
    )
    (net (code "39") (name "Net-(IC8-INT1)") (class "Default")
      (node (ref "IC8") (pin "12") (pinfunction "INT1_12") (pintype "open_collector"))
      (node (ref "Q7") (pin "2") (pinfunction "G_2") (pintype "passive"))
    )
    (net (code "40") (name "Net-(IC8-REGOUT)") (class "Default")
      (node (ref "C26") (pin "1") (pinfunction "1_1") (pintype "passive"))
      (node (ref "IC8") (pin "10") (pinfunction "REGOUT_10") (pintype "output"))
    )
    (net (code "41") (name "Net-(IC8-SCL{slash}SCLK)") (class "Default")
      (node (ref "IC8") (pin "23") (pinfunction "SCL/SCLK_23") (pintype "bidirectional"))
      (node (ref "Q6") (pin "1") (pinfunction "S_1") (pintype "passive"))
      (node (ref "RN2") (pin "6") (pinfunction "6_6") (pintype "passive"))
    )
    (net (code "42") (name "Net-(IC8-SDA{slash}SDI)") (class "Default")
      (node (ref "IC8") (pin "24") (pinfunction "SDA/SDI_24") (pintype "bidirectional"))
      (node (ref "Q6") (pin "4") (pinfunction "S_4") (pintype "passive"))
      (node (ref "RN2") (pin "5") (pinfunction "5_5") (pintype "passive"))
    )
    (net (code "43") (name "Net-(Q2-D)") (class "Default")
      (node (ref "Q2") (pin "3") (pinfunction "D_3") (pintype "passive"))
      (node (ref "X12") (pin "4") (pinfunction "VCC_4") (pintype "power_in"))
    )
    (net (code "44") (name "Net-(Q3-D)") (class "Default")
      (node (ref "Q3") (pin "3") (pinfunction "D_3") (pintype "passive"))
      (node (ref "X10") (pin "1") (pinfunction "1_1") (pintype "passive"))
    )
    (net (code "45") (name "Net-(Q4-D)") (class "Default")
      (node (ref "Q4") (pin "3") (pinfunction "D_3") (pintype "passive"))
      (node (ref "X3") (pin "2") (pinfunction "2_2") (pintype "bidirectional"))
      (node (ref "X5") (pin "2") (pinfunction "2_2") (pintype "bidirectional"))
      (node (ref "X6") (pin "2") (pinfunction "2_2") (pintype "bidirectional"))
    )
    (net (code "46") (name "Net-(Q5-D)") (class "Default")
      (node (ref "Q5") (pin "3") (pinfunction "D_3") (pintype "passive"))
      (node (ref "X4") (pin "2") (pinfunction "2_2") (pintype "bidirectional"))
    )
    (net (code "47") (name "Net-(RN1-Pad5)") (class "Default")
      (node (ref "RN1") (pin "5") (pinfunction "5_5") (pintype "passive"))
      (node (ref "X6") (pin "4") (pinfunction "4_4") (pintype "bidirectional"))
    )
    (net (code "48") (name "Net-(RN1-Pad6)") (class "Default")
      (node (ref "RN1") (pin "6") (pinfunction "6_6") (pintype "passive"))
      (node (ref "X6") (pin "3") (pinfunction "3_3") (pintype "bidirectional"))
    )
    (net (code "49") (name "Net-(RN1-Pad7)") (class "Default")
      (node (ref "RN1") (pin "7") (pinfunction "7_7") (pintype "passive"))
      (node (ref "X5") (pin "4") (pinfunction "4_4") (pintype "bidirectional"))
    )
    (net (code "50") (name "Net-(RN1-Pad8)") (class "Default")
      (node (ref "RN1") (pin "8") (pinfunction "8_8") (pintype "passive"))
      (node (ref "X5") (pin "3") (pinfunction "3_3") (pintype "bidirectional"))
    )
    (net (code "51") (name "Net-(RN3-Pad5)") (class "Default")
      (node (ref "RN3") (pin "5") (pinfunction "5_5") (pintype "passive"))
      (node (ref "X3") (pin "4") (pinfunction "4_4") (pintype "bidirectional"))
    )
    (net (code "52") (name "Net-(RN3-Pad6)") (class "Default")
      (node (ref "RN3") (pin "6") (pinfunction "6_6") (pintype "passive"))
      (node (ref "X3") (pin "3") (pinfunction "3_3") (pintype "bidirectional"))
    )
    (net (code "53") (name "Net-(RN3-Pad7)") (class "Default")
      (node (ref "RN3") (pin "7") (pinfunction "7_7") (pintype "passive"))
      (node (ref "X4") (pin "4") (pinfunction "4_4") (pintype "bidirectional"))
    )
    (net (code "54") (name "Net-(RN3-Pad8)") (class "Default")
      (node (ref "RN3") (pin "8") (pinfunction "8_8") (pintype "passive"))
      (node (ref "X4") (pin "3") (pinfunction "3_3") (pintype "bidirectional"))
    )
    (net (code "55") (name "Net-(RN4-Pad5)") (class "Default")
      (node (ref "RN4") (pin "5") (pinfunction "5_5") (pintype "passive"))
      (node (ref "RN5") (pin "5") (pinfunction "5_5") (pintype "passive"))
      (node (ref "RN5") (pin "6") (pinfunction "6_6") (pintype "passive"))
      (node (ref "X7") (pin "3") (pinfunction "3_3") (pintype "bidirectional"))
      (node (ref "X8") (pin "3") (pinfunction "3_3") (pintype "bidirectional"))
    )
    (net (code "56") (name "Net-(RN4-Pad6)") (class "Default")
      (node (ref "RN4") (pin "6") (pinfunction "6_6") (pintype "passive"))
      (node (ref "RN5") (pin "7") (pinfunction "7_7") (pintype "passive"))
      (node (ref "RN5") (pin "8") (pinfunction "8_8") (pintype "passive"))
      (node (ref "X7") (pin "4") (pinfunction "4_4") (pintype "bidirectional"))
      (node (ref "X8") (pin "4") (pinfunction "4_4") (pintype "bidirectional"))
    )
    (net (code "57") (name "Net-(SW1-C2)") (class "Default")
      (node (ref "R12") (pin "1") (pinfunction "1_1") (pintype "passive"))
      (node (ref "SW1") (pin "5") (pinfunction "C2_5") (pintype "bidirectional"))
    )
    (net (code "58") (name "Net-(X1-CC1)") (class "Default")
      (node (ref "R7") (pin "2") (pinfunction "2_2") (pintype "passive"))
      (node (ref "X1") (pin "A5") (pinfunction "CC1_A5") (pintype "passive"))
    )
    (net (code "59") (name "Net-(X1-CC2)") (class "Default")
      (node (ref "R6") (pin "2") (pinfunction "2_2") (pintype "passive"))
      (node (ref "X1") (pin "B5") (pinfunction "CC2_B5") (pintype "passive"))
    )
    (net (code "60") (name "PD_ENABLE") (class "Default")
      (node (ref "D5") (pin "A") (pinfunction "A_A") (pintype "passive"))
      (node (ref "IC3") (pin "25") (pinfunction "IO21_25") (pintype "bidirectional"))
    )
    (net (code "61") (name "PD_SENSE") (class "Default")
      (node (ref "D5") (pin "C") (pinfunction "C_C") (pintype "passive"))
      (node (ref "IC3") (pin "18") (pinfunction "IO14_18") (pintype "bidirectional"))
      (node (ref "R17") (pin "2") (pinfunction "2_2") (pintype "passive"))
    )
    (net (code "62") (name "QWIIC_SCL") (class "Default")
      (node (ref "IC3") (pin "36") (pinfunction "IO40_36") (pintype "bidirectional"))
      (node (ref "RN4") (pin "3") (pinfunction "3_3") (pintype "passive"))
    )
    (net (code "63") (name "QWIIC_SDA") (class "Default")
      (node (ref "IC3") (pin "35") (pinfunction "IO39_35") (pintype "bidirectional"))
      (node (ref "RN4") (pin "4") (pinfunction "4_4") (pintype "passive"))
    )
    (net (code "64") (name "SD_CS") (class "Default")
      (node (ref "IC3") (pin "14") (pinfunction "IO10_14") (pintype "bidirectional"))
      (node (ref "X12") (pin "2") (pinfunction "CD/DAT3_2") (pintype "bidirectional"))
    )
    (net (code "65") (name "SD_ENABLE") (class "Default")
      (node (ref "IC3") (pin "13") (pinfunction "IO9_13") (pintype "bidirectional"))
      (node (ref "Q2") (pin "1") (pinfunction "G_1") (pintype "passive"))
    )
    (net (code "66") (name "SD_MISO") (class "Default")
      (node (ref "IC3") (pin "17") (pinfunction "IO13_17") (pintype "bidirectional"))
      (node (ref "R13") (pin "2") (pinfunction "2_2") (pintype "passive"))
      (node (ref "X12") (pin "7") (pinfunction "DAT0_7") (pintype "bidirectional"))
    )
    (net (code "67") (name "SD_MOSI") (class "Default")
      (node (ref "IC3") (pin "15") (pinfunction "IO11_15") (pintype "bidirectional"))
      (node (ref "X12") (pin "3") (pinfunction "CMD_3") (pintype "input"))
    )
    (net (code "68") (name "SD_SCLK") (class "Default")
      (node (ref "IC3") (pin "16") (pinfunction "IO12_16") (pintype "bidirectional"))
      (node (ref "X12") (pin "5") (pinfunction "CLK_5") (pintype "input"))
    )
    (net (code "69") (name "UART_ENABLE") (class "Default")
      (node (ref "IC3") (pin "26") (pinfunction "IO26_26") (pintype "bidirectional"))
      (node (ref "Q5") (pin "1") (pinfunction "G_1") (pintype "passive"))
      (node (ref "R16") (pin "2") (pinfunction "2_2") (pintype "passive"))
    )
    (net (code "70") (name "UART_RXD") (class "Default")
      (node (ref "IC3") (pin "40") (pinfunction "RXD0_40") (pintype "bidirectional"))
      (node (ref "RN3") (pin "1") (pinfunction "1_1") (pintype "passive"))
    )
    (net (code "71") (name "UART_TXD") (class "Default")
      (node (ref "IC3") (pin "39") (pinfunction "TXD0_39") (pintype "bidirectional"))
      (node (ref "RN3") (pin "2") (pinfunction "2_2") (pintype "passive"))
    )
    (net (code "72") (name "USB_D+") (class "Default")
      (node (ref "IC3") (pin "24") (pinfunction "IO20_24") (pintype "bidirectional"))
      (node (ref "R5") (pin "2") (pinfunction "2_2") (pintype "passive"))
    )
    (net (code "73") (name "USB_D-") (class "Default")
      (node (ref "IC3") (pin "23") (pinfunction "IO19_23") (pintype "bidirectional"))
      (node (ref "R4") (pin "2") (pinfunction "2_2") (pintype "passive"))
    )
    (net (code "74") (name "VBAT") (class "Default")
      (node (ref "C13") (pin "1") (pinfunction "1_1") (pintype "passive"))
      (node (ref "C4") (pin "1") (pinfunction "1_1") (pintype "passive"))
      (node (ref "D2") (pin "6") (pinfunction "VIN2_6") (pintype "power_in"))
      (node (ref "IC2") (pin "3") (pinfunction "VBAT_3") (pintype "bidirectional"))
      (node (ref "IC4") (pin "6") (pinfunction "DRAIN_6") (pintype "passive"))
      (node (ref "Q1") (pin "6") (pinfunction "D_6") (pintype "passive"))
      (node (ref "Q1") (pin "7") (pinfunction "D_7") (pintype "passive"))
      (node (ref "X2") (pin "2") (pinfunction "2_2") (pintype "bidirectional"))
    )
    (net (code "75") (name "VUSB") (class "Default")
      (node (ref "C12") (pin "1") (pinfunction "1_1") (pintype "passive"))
      (node (ref "C5") (pin "1") (pinfunction "1_1") (pintype "passive"))
      (node (ref "D1") (pin "A") (pinfunction "A_A") (pintype "passive"))
      (node (ref "D2") (pin "3") (pinfunction "VIN1_3") (pintype "power_in"))
      (node (ref "D2") (pin "8") (pinfunction "ST_8") (pintype "open_collector"))
      (node (ref "F1") (pin "2") (pinfunction "3_2") (pintype "passive"))
      (node (ref "IC2") (pin "4") (pinfunction "VIN_4") (pintype "power_in"))
      (node (ref "IC5") (pin "6") (pinfunction "DRAIN_6") (pintype "passive"))
      (node (ref "Q1") (pin "3") (pinfunction "D_3") (pintype "passive"))
      (node (ref "Q1") (pin "8") (pinfunction "D_8") (pintype "passive"))
      (node (ref "R18") (pin "2") (pinfunction "2_2") (pintype "passive"))
      (node (ref "SW1") (pin "2") (pinfunction "C1_2") (pintype "bidirectional"))
      (node (ref "X13") (pin "1") (pinfunction "1_1") (pintype "bidirectional"))
    )
    (net (code "76") (name "XBEE_CS") (class "Default")
      (node (ref "IC3") (pin "29") (pinfunction "IO34_29") (pintype "bidirectional"))
      (node (ref "X11") (pin "7") (pinfunction "7_7") (pintype "passive"))
    )
    (net (code "77") (name "XBEE_ENABLE") (class "Default")
      (node (ref "IC3") (pin "37") (pinfunction "IO41_37") (pintype "bidirectional"))
      (node (ref "Q3") (pin "1") (pinfunction "G_1") (pintype "passive"))
      (node (ref "R14") (pin "2") (pinfunction "2_2") (pintype "passive"))
    )
    (net (code "78") (name "XBEE_INT") (class "Default")
      (node (ref "IC3") (pin "28") (pinfunction "IO33_28") (pintype "bidirectional"))
      (node (ref "X11") (pin "2") (pinfunction "2_2") (pintype "passive"))
    )
    (net (code "79") (name "XBEE_MISO") (class "Default")
      (node (ref "IC3") (pin "33") (pinfunction "IO37_33") (pintype "bidirectional"))
      (node (ref "X10") (pin "4") (pinfunction "4_4") (pintype "passive"))
    )
    (net (code "80") (name "XBEE_MOSI") (class "Default")
      (node (ref "IC3") (pin "31") (pinfunction "IO35_31") (pintype "bidirectional"))
      (node (ref "X11") (pin "1") (pinfunction "1_1") (pintype "passive"))
    )
    (net (code "81") (name "XBEE_RESET") (class "Default")
      (node (ref "IC3") (pin "34") (pinfunction "IO38_34") (pintype "bidirectional"))
      (node (ref "X10") (pin "5") (pinfunction "5_5") (pintype "passive"))
    )
    (net (code "82") (name "XBEE_RXD") (class "Default")
      (node (ref "IC3") (pin "22") (pinfunction "IO18_22") (pintype "bidirectional"))
      (node (ref "X10") (pin "2") (pinfunction "2_2") (pintype "passive"))
    )
    (net (code "83") (name "XBEE_SCLK") (class "Default")
      (node (ref "IC3") (pin "32") (pinfunction "IO36_32") (pintype "bidirectional"))
      (node (ref "X11") (pin "8") (pinfunction "8_8") (pintype "passive"))
    )
    (net (code "84") (name "XBEE_TXD") (class "Default")
      (node (ref "IC3") (pin "21") (pinfunction "IO17_21") (pintype "bidirectional"))
      (node (ref "X10") (pin "3") (pinfunction "3_3") (pintype "passive"))
    )
    (net (code "85") (name "unconnected-(D4-DOUT-Pad2)") (class "Default")
      (node (ref "D4") (pin "2") (pinfunction "DOUT_2") (pintype "output"))
    )
    (net (code "86") (name "unconnected-(IC6-AUX_CL-Pad7)") (class "Default")
      (node (ref "IC6") (pin "7") (pinfunction "AUX_CL_7") (pintype "bidirectional"))
    )
    (net (code "87") (name "unconnected-(IC6-AUX_DA-Pad6)") (class "Default")
      (node (ref "IC6") (pin "6") (pinfunction "AUX_DA_6") (pintype "bidirectional"))
    )
    (net (code "88") (name "unconnected-(IC8-AUX_CL-Pad7)") (class "Default")
      (node (ref "IC8") (pin "7") (pinfunction "AUX_CL_7") (pintype "bidirectional"))
    )
    (net (code "89") (name "unconnected-(IC8-AUX_DA-Pad21)") (class "Default")
      (node (ref "IC8") (pin "21") (pinfunction "AUX_DA_21") (pintype "bidirectional"))
    )
    (net (code "90") (name "unconnected-(Q7B-D-Pad3)") (class "Default")
      (node (ref "Q7") (pin "3") (pinfunction "D_3") (pintype "passive"))
    )
    (net (code "91") (name "unconnected-(RN4-Pad1)") (class "Default")
      (node (ref "RN4") (pin "1") (pinfunction "1_1") (pintype "passive"))
    )
    (net (code "92") (name "unconnected-(RN4-Pad2)") (class "Default")
      (node (ref "RN4") (pin "2") (pinfunction "2_2") (pintype "passive"))
    )
    (net (code "93") (name "unconnected-(RN4-Pad7)") (class "Default")
      (node (ref "RN4") (pin "7") (pinfunction "7_7") (pintype "passive"))
    )
    (net (code "94") (name "unconnected-(RN4-Pad8)") (class "Default")
      (node (ref "RN4") (pin "8") (pinfunction "8_8") (pintype "passive"))
    )
    (net (code "95") (name "unconnected-(SW1-NO1-Pad1)") (class "Default")
      (node (ref "SW1") (pin "1") (pinfunction "NO1_1") (pintype "bidirectional"))
    )
    (net (code "96") (name "unconnected-(X10-Pad6)") (class "Default")
      (node (ref "X10") (pin "6") (pinfunction "6_6") (pintype "passive"))
    )
    (net (code "97") (name "unconnected-(X10-Pad7)") (class "Default")
      (node (ref "X10") (pin "7") (pinfunction "7_7") (pintype "passive"))
    )
    (net (code "98") (name "unconnected-(X10-Pad8)") (class "Default")
      (node (ref "X10") (pin "8") (pinfunction "8_8") (pintype "passive"))
    )
    (net (code "99") (name "unconnected-(X10-Pad9)") (class "Default")
      (node (ref "X10") (pin "9") (pinfunction "9_9") (pintype "passive"))
    )
    (net (code "100") (name "unconnected-(X11-Pad3)") (class "Default")
      (node (ref "X11") (pin "3") (pinfunction "3_3") (pintype "passive"))
    )
    (net (code "101") (name "unconnected-(X11-Pad4)") (class "Default")
      (node (ref "X11") (pin "4") (pinfunction "4_4") (pintype "passive"))
    )
    (net (code "102") (name "unconnected-(X11-Pad5)") (class "Default")
      (node (ref "X11") (pin "5") (pinfunction "5_5") (pintype "passive"))
    )
    (net (code "103") (name "unconnected-(X11-Pad6)") (class "Default")
      (node (ref "X11") (pin "6") (pinfunction "6_6") (pintype "passive"))
    )
    (net (code "104") (name "unconnected-(X11-Pad9)") (class "Default")
      (node (ref "X11") (pin "9") (pinfunction "9_9") (pintype "passive"))
    )
    (net (code "105") (name "unconnected-(X11-Pad10)") (class "Default")
      (node (ref "X11") (pin "10") (pinfunction "10_10") (pintype "passive"))
    )
    (net (code "106") (name "unconnected-(X12-CD-Pad9)") (class "Default")
      (node (ref "X12") (pin "9") (pinfunction "CD_9") (pintype "passive"))
    )
    (net (code "107") (name "unconnected-(X12-DAT1-Pad8)") (class "Default")
      (node (ref "X12") (pin "8") (pinfunction "DAT1_8") (pintype "bidirectional"))
    )
    (net (code "108") (name "unconnected-(X12-DAT2-Pad1)") (class "Default")
      (node (ref "X12") (pin "1") (pinfunction "DAT2_1") (pintype "bidirectional"))
    )
  )
)
